# atmega16u2custom.net
KiCad netlist of a schematic drawn in EAGLE
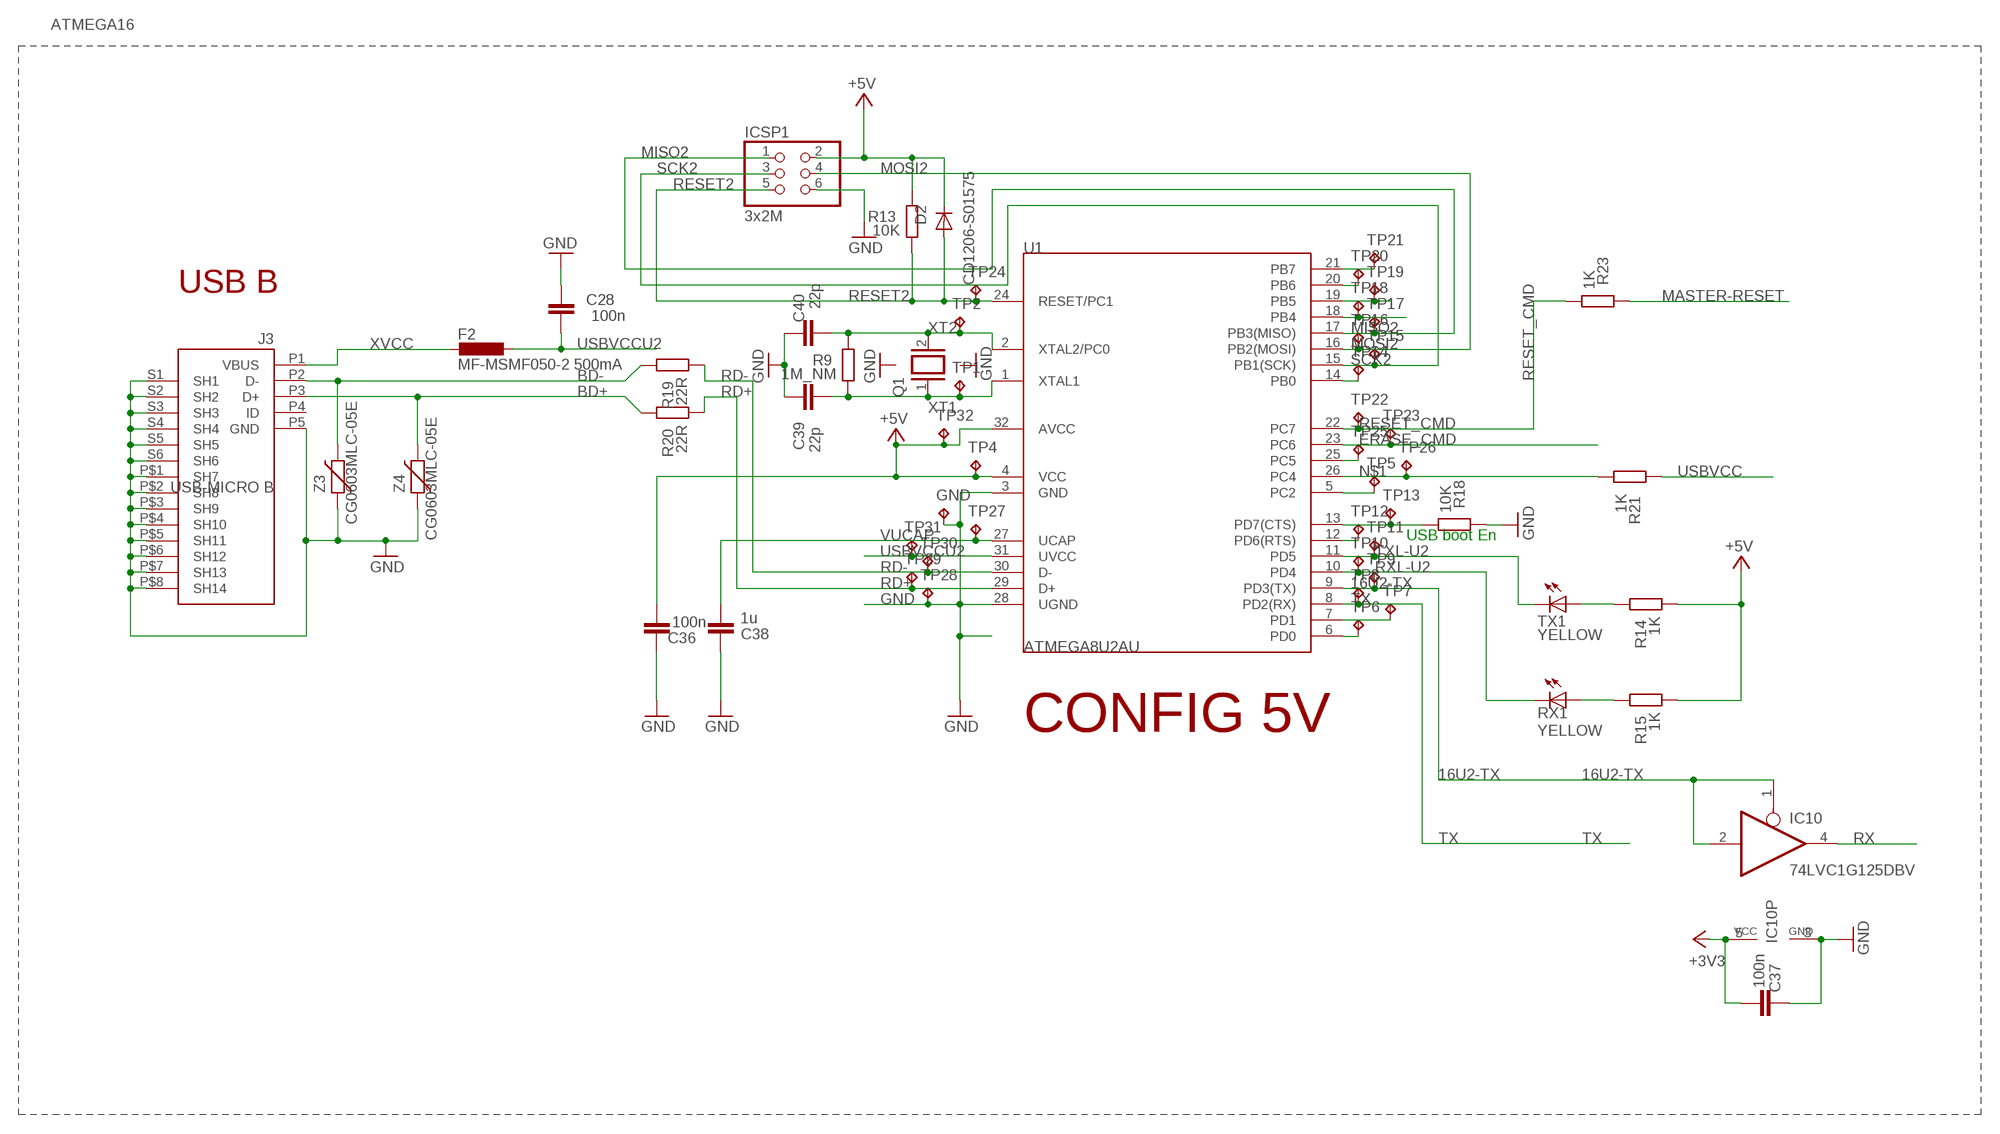
[diagram p0: schematic, sheet 1]

(export (version "E")
  (design (tool "Eeschema 10.0.6"))
  (components
    (comp (ref "C28")
      (value "100n")
      (footprint "eagle-import:C0805")
      (libsource (lib "eagle-import") (part "C-EUC0805"))
    )
    (comp (ref "C36")
      (value "100n")
      (footprint "eagle-import:C0805")
      (libsource (lib "eagle-import") (part "C-EUC0805"))
    )
    (comp (ref "C37")
      (value "100n")
      (footprint "eagle-import:C0805")
      (libsource (lib "eagle-import") (part "C-EUC0805"))
    )
    (comp (ref "C38")
      (value "1u")
      (footprint "eagle-import:C0805")
      (libsource (lib "eagle-import") (part "C-EUC0805"))
    )
    (comp (ref "C39")
      (value "22p")
      (footprint "eagle-import:C0805")
      (libsource (lib "eagle-import") (part "C-EUC0805"))
    )
    (comp (ref "C40")
      (value "22p")
      (footprint "eagle-import:C0805")
      (libsource (lib "eagle-import") (part "C-EUC0805"))
    )
    (comp (ref "D2")
      (value "CD1206-S01575")
      (footprint "eagle-import:MINIMELF")
      (libsource (lib "eagle-import") (part "DIODE-MINIMELF"))
    )
    (comp (ref "F2")
      (value "MF-MSMF050-2 500mA")
      (footprint "eagle-import:L1812")
      (libsource (lib "eagle-import") (part "L-EUL1812"))
    )
    (comp (ref "GND")
      (value "TPB1,27")
      (footprint "eagle-import:B1,27")
      (libsource (lib "eagle-import") (part "TPB1,27"))
    )
    (comp (ref "IC10")
      (value "74LVC1G125DBV")
      (footprint "eagle-import:SOT23-5")
      (libsource (lib "eagle-import") (part "741G125DBVLVC"))
    )
    (comp (ref "ICSP1")
      (value "3x2M")
      (footprint "eagle-import:2X03")
      (libsource (lib "eagle-import") (part "PINHD-2X3"))
    )
    (comp (ref "J3")
      (value "USB-MICRO B")
      (footprint "eagle-import:CON2_USB_MICRO_B_AT")
      (libsource (lib "eagle-import") (part "MYCON2_USB-MINI-B"))
    )
    (comp (ref "Q1")
      (value "XTAL/S")
      (footprint "eagle-import:QS")
      (libsource (lib "eagle-import") (part "XTAL/S"))
    )
    (comp (ref "R9")
      (value "1M_NM")
      (footprint "eagle-import:R0805")
      (libsource (lib "eagle-import") (part "R-EU_R0805"))
    )
    (comp (ref "R13")
      (value "10K")
      (footprint "eagle-import:R0805")
      (libsource (lib "eagle-import") (part "R-EU_R0805"))
    )
    (comp (ref "R14")
      (value "1K")
      (footprint "eagle-import:R0805")
      (libsource (lib "eagle-import") (part "R-EU_R0805"))
    )
    (comp (ref "R15")
      (value "1K")
      (footprint "eagle-import:R0805")
      (libsource (lib "eagle-import") (part "R-EU_R0805"))
    )
    (comp (ref "R18")
      (value "10K")
      (footprint "eagle-import:R0805")
      (libsource (lib "eagle-import") (part "R-EU_R0805"))
    )
    (comp (ref "R19")
      (value "22R")
      (footprint "eagle-import:R0805")
      (libsource (lib "eagle-import") (part "R-EU_R0805"))
    )
    (comp (ref "R20")
      (value "22R")
      (footprint "eagle-import:R0805")
      (libsource (lib "eagle-import") (part "R-EU_R0805"))
    )
    (comp (ref "R21")
      (value "1K")
      (footprint "eagle-import:R0805")
      (libsource (lib "eagle-import") (part "R-EU_R0805"))
    )
    (comp (ref "R23")
      (value "1K")
      (footprint "eagle-import:R0805")
      (libsource (lib "eagle-import") (part "R-EU_R0805"))
    )
    (comp (ref "RX1")
      (value "YELLOW")
      (footprint "eagle-import:CHIP-LED0805")
      (libsource (lib "eagle-import") (part "LEDCHIP-LED0805"))
    )
    (comp (ref "TP1")
      (value "TPB1,27")
      (footprint "eagle-import:B1,27")
      (libsource (lib "eagle-import") (part "TPB1,27"))
    )
    (comp (ref "TP2")
      (value "TPB1,27")
      (footprint "eagle-import:B1,27")
      (libsource (lib "eagle-import") (part "TPB1,27"))
    )
    (comp (ref "TP4")
      (value "TPB1,27")
      (footprint "eagle-import:B1,27")
      (libsource (lib "eagle-import") (part "TPB1,27"))
    )
    (comp (ref "TP5")
      (value "TPB1,27")
      (footprint "eagle-import:B1,27")
      (libsource (lib "eagle-import") (part "TPB1,27"))
    )
    (comp (ref "TP6")
      (value "TPB1,27")
      (footprint "eagle-import:B1,27")
      (libsource (lib "eagle-import") (part "TPB1,27"))
    )
    (comp (ref "TP7")
      (value "TPB1,27")
      (footprint "eagle-import:B1,27")
      (libsource (lib "eagle-import") (part "TPB1,27"))
    )
    (comp (ref "TP8")
      (value "TPB1,27")
      (footprint "eagle-import:B1,27")
      (libsource (lib "eagle-import") (part "TPB1,27"))
    )
    (comp (ref "TP9")
      (value "TPB1,27")
      (footprint "eagle-import:B1,27")
      (libsource (lib "eagle-import") (part "TPB1,27"))
    )
    (comp (ref "TP10")
      (value "TPB1,27")
      (footprint "eagle-import:B1,27")
      (libsource (lib "eagle-import") (part "TPB1,27"))
    )
    (comp (ref "TP11")
      (value "TPB1,27")
      (footprint "eagle-import:B1,27")
      (libsource (lib "eagle-import") (part "TPB1,27"))
    )
    (comp (ref "TP12")
      (value "TPB1,27")
      (footprint "eagle-import:B1,27")
      (libsource (lib "eagle-import") (part "TPB1,27"))
    )
    (comp (ref "TP13")
      (value "TPB1,27")
      (footprint "eagle-import:B1,27")
      (libsource (lib "eagle-import") (part "TPB1,27"))
    )
    (comp (ref "TP14")
      (value "TPB1,27")
      (footprint "eagle-import:B1,27")
      (libsource (lib "eagle-import") (part "TPB1,27"))
    )
    (comp (ref "TP15")
      (value "TPB1,27")
      (footprint "eagle-import:B1,27")
      (libsource (lib "eagle-import") (part "TPB1,27"))
    )
    (comp (ref "TP16")
      (value "TPB1,27")
      (footprint "eagle-import:B1,27")
      (libsource (lib "eagle-import") (part "TPB1,27"))
    )
    (comp (ref "TP17")
      (value "TPB1,27")
      (footprint "eagle-import:B1,27")
      (libsource (lib "eagle-import") (part "TPB1,27"))
    )
    (comp (ref "TP18")
      (value "TPB1,27")
      (footprint "eagle-import:B1,27")
      (libsource (lib "eagle-import") (part "TPB1,27"))
    )
    (comp (ref "TP19")
      (value "TPB1,27")
      (footprint "eagle-import:B1,27")
      (libsource (lib "eagle-import") (part "TPB1,27"))
    )
    (comp (ref "TP20")
      (value "TPB1,27")
      (footprint "eagle-import:B1,27")
      (libsource (lib "eagle-import") (part "TPB1,27"))
    )
    (comp (ref "TP21")
      (value "TPB1,27")
      (footprint "eagle-import:B1,27")
      (libsource (lib "eagle-import") (part "TPB1,27"))
    )
    (comp (ref "TP22")
      (value "TPB1,27")
      (footprint "eagle-import:B1,27")
      (libsource (lib "eagle-import") (part "TPB1,27"))
    )
    (comp (ref "TP23")
      (value "TPB1,27")
      (footprint "eagle-import:B1,27")
      (libsource (lib "eagle-import") (part "TPB1,27"))
    )
    (comp (ref "TP24")
      (value "TPB1,27")
      (footprint "eagle-import:B1,27")
      (libsource (lib "eagle-import") (part "TPB1,27"))
    )
    (comp (ref "TP25")
      (value "TPB1,27")
      (footprint "eagle-import:B1,27")
      (libsource (lib "eagle-import") (part "TPB1,27"))
    )
    (comp (ref "TP26")
      (value "TPB1,27")
      (footprint "eagle-import:B1,27")
      (libsource (lib "eagle-import") (part "TPB1,27"))
    )
    (comp (ref "TP27")
      (value "TPB1,27")
      (footprint "eagle-import:B1,27")
      (libsource (lib "eagle-import") (part "TPB1,27"))
    )
    (comp (ref "TP28")
      (value "TPB1,27")
      (footprint "eagle-import:B1,27")
      (libsource (lib "eagle-import") (part "TPB1,27"))
    )
    (comp (ref "TP29")
      (value "TPB1,27")
      (footprint "eagle-import:B1,27")
      (libsource (lib "eagle-import") (part "TPB1,27"))
    )
    (comp (ref "TP30")
      (value "TPB1,27")
      (footprint "eagle-import:B1,27")
      (libsource (lib "eagle-import") (part "TPB1,27"))
    )
    (comp (ref "TP31")
      (value "TPB1,27")
      (footprint "eagle-import:B1,27")
      (libsource (lib "eagle-import") (part "TPB1,27"))
    )
    (comp (ref "TP32")
      (value "TPB1,27")
      (footprint "eagle-import:B1,27")
      (libsource (lib "eagle-import") (part "TPB1,27"))
    )
    (comp (ref "TX1")
      (value "YELLOW")
      (footprint "eagle-import:CHIP-LED0805")
      (libsource (lib "eagle-import") (part "LEDCHIP-LED0805"))
    )
    (comp (ref "U1")
      (value "ATMEGA8U2AU")
      (footprint "eagle-import:TQFP32-08")
      (libsource (lib "eagle-import") (part "ATMEGA8U2AU"))
    )
    (comp (ref "Z3")
      (value "CG0603MLC-05E")
      (footprint "eagle-import:CT_CN0603")
      (libsource (lib "eagle-import") (part "VARISTORCN0603"))
    )
    (comp (ref "Z4")
      (value "CG0603MLC-05E")
      (footprint "eagle-import:CT_CN0603")
      (libsource (lib "eagle-import") (part "VARISTORCN0603"))
    )
  )
  (nets
    (net (code "1") (name "+3V3") (class "Default")
      (node (ref "C37") (pin "1") (pinfunction "1_1") (pintype "passive"))
      (node (ref "IC10") (pin "5") (pinfunction "VCC_5") (pintype "power_in"))
    )
    (net (code "2") (name "+5V") (class "Default")
      (node (ref "C36") (pin "1") (pinfunction "1_1") (pintype "passive"))
      (node (ref "D2") (pin "C") (pinfunction "C_C") (pintype "passive"))
      (node (ref "ICSP1") (pin "2") (pinfunction "2_2") (pintype "passive"))
      (node (ref "R13") (pin "2") (pinfunction "2_2") (pintype "passive"))
      (node (ref "R14") (pin "1") (pinfunction "1_1") (pintype "passive"))
      (node (ref "R15") (pin "1") (pinfunction "1_1") (pintype "passive"))
      (node (ref "TP32") (pin "TP") (pinfunction "TP_TP") (pintype "input"))
      (node (ref "TP4") (pin "TP") (pinfunction "TP_TP") (pintype "input"))
      (node (ref "U1") (pin "32") (pinfunction "AVCC_32") (pintype "bidirectional"))
      (node (ref "U1") (pin "4") (pinfunction "VCC_4") (pintype "bidirectional"))
    )
    (net (code "3") (name "/16U2-TX") (class "Default")
      (node (ref "IC10") (pin "1") (pinfunction "OE_1") (pintype "input"))
      (node (ref "IC10") (pin "2") (pinfunction "I_2") (pintype "input"))
      (node (ref "TP9") (pin "TP") (pinfunction "TP_TP") (pintype "input"))
      (node (ref "U1") (pin "9") (pinfunction "PD3(TX)_9") (pintype "bidirectional"))
    )
    (net (code "4") (name "/BD+") (class "Default")
      (node (ref "J3") (pin "P3") (pinfunction "D+_P3") (pintype "bidirectional"))
      (node (ref "R20") (pin "2") (pinfunction "2_2") (pintype "passive"))
      (node (ref "Z4") (pin "2") (pinfunction "2_2") (pintype "passive"))
    )
    (net (code "5") (name "/BD-") (class "Default")
      (node (ref "J3") (pin "P2") (pinfunction "D-_P2") (pintype "bidirectional"))
      (node (ref "R19") (pin "2") (pinfunction "2_2") (pintype "passive"))
      (node (ref "Z3") (pin "2") (pinfunction "2_2") (pintype "passive"))
    )
    (net (code "6") (name "/ERASE_CMD") (class "Default")
      (node (ref "TP23") (pin "TP") (pinfunction "TP_TP") (pintype "input"))
      (node (ref "U1") (pin "23") (pinfunction "PC6_23") (pintype "bidirectional"))
    )
    (net (code "7") (name "/MASTER-RESET") (class "Default")
      (node (ref "R23") (pin "2") (pinfunction "2_2") (pintype "passive"))
    )
    (net (code "8") (name "/MISO2") (class "Default")
      (node (ref "ICSP1") (pin "1") (pinfunction "1_1") (pintype "passive"))
      (node (ref "TP17") (pin "TP") (pinfunction "TP_TP") (pintype "input"))
      (node (ref "U1") (pin "17") (pinfunction "PB3(MISO)_17") (pintype "bidirectional"))
    )
    (net (code "9") (name "/MOSI2") (class "Default")
      (node (ref "ICSP1") (pin "4") (pinfunction "4_4") (pintype "passive"))
      (node (ref "TP16") (pin "TP") (pinfunction "TP_TP") (pintype "input"))
      (node (ref "U1") (pin "16") (pinfunction "PB2(MOSI)_16") (pintype "bidirectional"))
    )
    (net (code "10") (name "/N$1") (class "Default")
      (node (ref "R21") (pin "1") (pinfunction "1_1") (pintype "passive"))
      (node (ref "TP26") (pin "TP") (pinfunction "TP_TP") (pintype "input"))
      (node (ref "U1") (pin "26") (pinfunction "PC4_26") (pintype "bidirectional"))
    )
    (net (code "11") (name "/RD+") (class "Default")
      (node (ref "R20") (pin "1") (pinfunction "1_1") (pintype "passive"))
      (node (ref "TP29") (pin "TP") (pinfunction "TP_TP") (pintype "input"))
      (node (ref "U1") (pin "29") (pinfunction "D+_29") (pintype "bidirectional"))
    )
    (net (code "12") (name "/RD-") (class "Default")
      (node (ref "R19") (pin "1") (pinfunction "1_1") (pintype "passive"))
      (node (ref "TP30") (pin "TP") (pinfunction "TP_TP") (pintype "input"))
      (node (ref "U1") (pin "30") (pinfunction "D-_30") (pintype "bidirectional"))
    )
    (net (code "13") (name "/RESET2") (class "Default")
      (node (ref "D2") (pin "A") (pinfunction "A_A") (pintype "passive"))
      (node (ref "ICSP1") (pin "5") (pinfunction "5_5") (pintype "passive"))
      (node (ref "R13") (pin "1") (pinfunction "1_1") (pintype "passive"))
      (node (ref "TP24") (pin "TP") (pinfunction "TP_TP") (pintype "input"))
      (node (ref "U1") (pin "24") (pinfunction "RESET/PC1_24") (pintype "bidirectional"))
    )
    (net (code "14") (name "/RESET_CMD") (class "Default")
      (node (ref "R23") (pin "1") (pinfunction "1_1") (pintype "passive"))
      (node (ref "TP22") (pin "TP") (pinfunction "TP_TP") (pintype "input"))
      (node (ref "U1") (pin "22") (pinfunction "PC7_22") (pintype "bidirectional"))
    )
    (net (code "15") (name "/RX") (class "Default")
      (node (ref "IC10") (pin "4") (pinfunction "O_4") (pintype "tri_state"))
    )
    (net (code "16") (name "/RXL-U2") (class "Default")
      (node (ref "RX1") (pin "C") (pinfunction "C_C") (pintype "passive"))
      (node (ref "TP10") (pin "TP") (pinfunction "TP_TP") (pintype "input"))
      (node (ref "U1") (pin "10") (pinfunction "PD4_10") (pintype "bidirectional"))
    )
    (net (code "17") (name "/SCK2") (class "Default")
      (node (ref "ICSP1") (pin "3") (pinfunction "3_3") (pintype "passive"))
      (node (ref "TP15") (pin "TP") (pinfunction "TP_TP") (pintype "input"))
      (node (ref "U1") (pin "15") (pinfunction "PB1(SCK)_15") (pintype "bidirectional"))
    )
    (net (code "18") (name "/TX") (class "Default")
      (node (ref "TP8") (pin "TP") (pinfunction "TP_TP") (pintype "input"))
      (node (ref "U1") (pin "8") (pinfunction "PD2(RX)_8") (pintype "bidirectional"))
    )
    (net (code "19") (name "/TXL-U2") (class "Default")
      (node (ref "TP11") (pin "TP") (pinfunction "TP_TP") (pintype "input"))
      (node (ref "TX1") (pin "C") (pinfunction "C_C") (pintype "passive"))
      (node (ref "U1") (pin "11") (pinfunction "PD5_11") (pintype "bidirectional"))
    )
    (net (code "20") (name "/USBVCC") (class "Default")
      (node (ref "R21") (pin "2") (pinfunction "2_2") (pintype "passive"))
    )
    (net (code "21") (name "/USBVCCU2") (class "Default")
      (node (ref "C28") (pin "1") (pinfunction "1_1") (pintype "passive"))
      (node (ref "F2") (pin "1") (pinfunction "1_1") (pintype "passive"))
      (node (ref "TP31") (pin "TP") (pinfunction "TP_TP") (pintype "input"))
      (node (ref "U1") (pin "31") (pinfunction "UVCC_31") (pintype "bidirectional"))
    )
    (net (code "22") (name "/VUCAP") (class "Default")
      (node (ref "C38") (pin "1") (pinfunction "1_1") (pintype "passive"))
      (node (ref "TP27") (pin "TP") (pinfunction "TP_TP") (pintype "input"))
      (node (ref "U1") (pin "27") (pinfunction "UCAP_27") (pintype "bidirectional"))
    )
    (net (code "23") (name "/XT1") (class "Default")
      (node (ref "C39") (pin "1") (pinfunction "1_1") (pintype "passive"))
      (node (ref "Q1") (pin "1") (pinfunction "1_1") (pintype "passive"))
      (node (ref "R9") (pin "1") (pinfunction "1_1") (pintype "passive"))
      (node (ref "TP1") (pin "TP") (pinfunction "TP_TP") (pintype "input"))
      (node (ref "U1") (pin "1") (pinfunction "XTAL1_1") (pintype "bidirectional"))
    )
    (net (code "24") (name "/XT2") (class "Default")
      (node (ref "C40") (pin "1") (pinfunction "1_1") (pintype "passive"))
      (node (ref "Q1") (pin "2") (pinfunction "2_2") (pintype "passive"))
      (node (ref "R9") (pin "2") (pinfunction "2_2") (pintype "passive"))
      (node (ref "TP2") (pin "TP") (pinfunction "TP_TP") (pintype "input"))
      (node (ref "U1") (pin "2") (pinfunction "XTAL2/PC0_2") (pintype "bidirectional"))
    )
    (net (code "25") (name "/XVCC") (class "Default")
      (node (ref "F2") (pin "2") (pinfunction "2_2") (pintype "passive"))
      (node (ref "J3") (pin "P1") (pinfunction "VBUS_P1") (pintype "power_in"))
    )
    (net (code "26") (name "GND") (class "Default")
      (node (ref "C28") (pin "2") (pinfunction "2_2") (pintype "passive"))
      (node (ref "C36") (pin "2") (pinfunction "2_2") (pintype "passive"))
      (node (ref "C37") (pin "2") (pinfunction "2_2") (pintype "passive"))
      (node (ref "C38") (pin "2") (pinfunction "2_2") (pintype "passive"))
      (node (ref "C39") (pin "2") (pinfunction "2_2") (pintype "passive"))
      (node (ref "C40") (pin "2") (pinfunction "2_2") (pintype "passive"))
      (node (ref "GND") (pin "TP") (pinfunction "TP_TP") (pintype "input"))
      (node (ref "IC10") (pin "3") (pinfunction "GND_3") (pintype "power_in"))
      (node (ref "ICSP1") (pin "6") (pinfunction "6_6") (pintype "passive"))
      (node (ref "J3") (pin "P$1") (pinfunction "SH7_P$1") (pintype "passive"))
      (node (ref "J3") (pin "P$2") (pinfunction "SH8_P$2") (pintype "passive"))
      (node (ref "J3") (pin "P$3") (pinfunction "SH9_P$3") (pintype "passive"))
      (node (ref "J3") (pin "P$4") (pinfunction "SH10_P$4") (pintype "passive"))
      (node (ref "J3") (pin "P$5") (pinfunction "SH11_P$5") (pintype "passive"))
      (node (ref "J3") (pin "P$6") (pinfunction "SH12_P$6") (pintype "passive"))
      (node (ref "J3") (pin "P$7") (pinfunction "SH13_P$7") (pintype "passive"))
      (node (ref "J3") (pin "P$8") (pinfunction "SH14_P$8") (pintype "passive"))
      (node (ref "J3") (pin "P5") (pinfunction "GND_P5") (pintype "passive"))
      (node (ref "J3") (pin "S1") (pinfunction "SH1_S1") (pintype "passive"))
      (node (ref "J3") (pin "S2") (pinfunction "SH2_S2") (pintype "passive"))
      (node (ref "J3") (pin "S3") (pinfunction "SH3_S3") (pintype "passive"))
      (node (ref "J3") (pin "S4") (pinfunction "SH4_S4") (pintype "passive"))
      (node (ref "J3") (pin "S5") (pinfunction "SH5_S5") (pintype "passive"))
      (node (ref "J3") (pin "S6") (pinfunction "SH6_S6") (pintype "passive"))
      (node (ref "R18") (pin "2") (pinfunction "2_2") (pintype "passive"))
      (node (ref "TP28") (pin "TP") (pinfunction "TP_TP") (pintype "input"))
      (node (ref "U1") (pin "28") (pinfunction "UGND_28") (pintype "bidirectional"))
      (node (ref "U1") (pin "3") (pinfunction "GND_3") (pintype "bidirectional"))
      (node (ref "Z3") (pin "1") (pinfunction "1_1") (pintype "passive"))
      (node (ref "Z4") (pin "1") (pinfunction "1_1") (pintype "passive"))
    )
    (net (code "27") (name "Net-(R14-Pad2)") (class "Default")
      (node (ref "R14") (pin "2") (pinfunction "2_2") (pintype "passive"))
      (node (ref "TX1") (pin "A") (pinfunction "A_A") (pintype "passive"))
    )
    (net (code "28") (name "Net-(R15-Pad2)") (class "Default")
      (node (ref "R15") (pin "2") (pinfunction "2_2") (pintype "passive"))
      (node (ref "RX1") (pin "A") (pinfunction "A_A") (pintype "passive"))
    )
    (net (code "29") (name "Net-(U1-PB0)") (class "Default")
      (node (ref "TP14") (pin "TP") (pinfunction "TP_TP") (pintype "input"))
      (node (ref "U1") (pin "14") (pinfunction "PB0_14") (pintype "bidirectional"))
    )
    (net (code "30") (name "Net-(U1-PB4)") (class "Default")
      (node (ref "TP18") (pin "TP") (pinfunction "TP_TP") (pintype "input"))
      (node (ref "U1") (pin "18") (pinfunction "PB4_18") (pintype "bidirectional"))
    )
    (net (code "31") (name "Net-(U1-PB5)") (class "Default")
      (node (ref "TP19") (pin "TP") (pinfunction "TP_TP") (pintype "input"))
      (node (ref "U1") (pin "19") (pinfunction "PB5_19") (pintype "bidirectional"))
    )
    (net (code "32") (name "Net-(U1-PB6)") (class "Default")
      (node (ref "TP20") (pin "TP") (pinfunction "TP_TP") (pintype "input"))
      (node (ref "U1") (pin "20") (pinfunction "PB6_20") (pintype "bidirectional"))
    )
    (net (code "33") (name "Net-(U1-PB7)") (class "Default")
      (node (ref "TP21") (pin "TP") (pinfunction "TP_TP") (pintype "input"))
      (node (ref "U1") (pin "21") (pinfunction "PB7_21") (pintype "bidirectional"))
    )
    (net (code "34") (name "Net-(U1-PC2)") (class "Default")
      (node (ref "TP5") (pin "TP") (pinfunction "TP_TP") (pintype "input"))
      (node (ref "U1") (pin "5") (pinfunction "PC2_5") (pintype "bidirectional"))
    )
    (net (code "35") (name "Net-(U1-PC5)") (class "Default")
      (node (ref "TP25") (pin "TP") (pinfunction "TP_TP") (pintype "input"))
      (node (ref "U1") (pin "25") (pinfunction "PC5_25") (pintype "bidirectional"))
    )
    (net (code "36") (name "Net-(U1-PD0)") (class "Default")
      (node (ref "TP6") (pin "TP") (pinfunction "TP_TP") (pintype "input"))
      (node (ref "U1") (pin "6") (pinfunction "PD0_6") (pintype "bidirectional"))
    )
    (net (code "37") (name "Net-(U1-PD1)") (class "Default")
      (node (ref "TP7") (pin "TP") (pinfunction "TP_TP") (pintype "input"))
      (node (ref "U1") (pin "7") (pinfunction "PD1_7") (pintype "bidirectional"))
    )
    (net (code "38") (name "Net-(U1-PD6(RTS))") (class "Default")
      (node (ref "TP12") (pin "TP") (pinfunction "TP_TP") (pintype "input"))
      (node (ref "U1") (pin "12") (pinfunction "PD6(RTS)_12") (pintype "bidirectional"))
    )
    (net (code "39") (name "Net-(U1-PD7(CTS))") (class "Default")
      (node (ref "R18") (pin "1") (pinfunction "1_1") (pintype "passive"))
      (node (ref "TP13") (pin "TP") (pinfunction "TP_TP") (pintype "input"))
      (node (ref "U1") (pin "13") (pinfunction "PD7(CTS)_13") (pintype "bidirectional"))
    )
    (net (code "40") (name "unconnected-(J3-ID-PadP4)") (class "Default")
      (node (ref "J3") (pin "P4") (pinfunction "ID_P4") (pintype "bidirectional"))
    )
  )
)
